# PCB-CARR-SL45.net
KiCad netlist of a schematic drawn in EAGLE
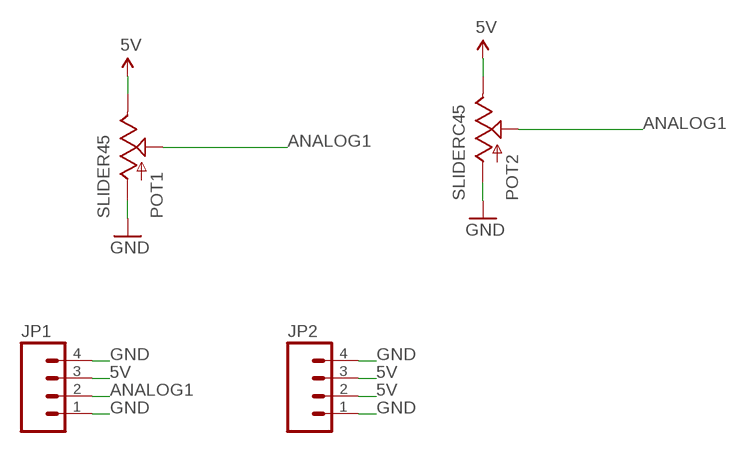
[diagram p0: schematic, sheet 1]

(export (version "E")
  (design (tool "Eeschema 10.0.6"))
  (components
    (comp (ref "JP1")
      (value "M04PTH")
      (footprint "eagle-import:1X04")
      (libsource (lib "eagle-import") (part "M04PTH"))
    )
    (comp (ref "JP2")
      (value "M04PTH")
      (footprint "eagle-import:1X04")
      (libsource (lib "eagle-import") (part "M04PTH"))
    )
    (comp (ref "POT1")
      (value "SLIDER45")
      (footprint "eagle-import:SLIDER45")
      (libsource (lib "eagle-import") (part "SLIDER45"))
    )
    (comp (ref "POT2")
      (value "SLIDERC45")
      (footprint "eagle-import:SLIDER45-CAR1")
      (libsource (lib "eagle-import") (part "SLIDERC45"))
    )
  )
  (nets
    (net (code "1") (name "/ANALOG1") (class "Default")
      (node (ref "JP1") (pin "2") (pinfunction "2_2") (pintype "passive"))
      (node (ref "POT1") (pin "2A") (pinfunction "S_2A") (pintype "passive"))
      (node (ref "POT2") (pin "2A") (pinfunction "S_2A") (pintype "passive"))
    )
    (net (code "2") (name "5V") (class "Default")
      (node (ref "JP1") (pin "3") (pinfunction "3_3") (pintype "passive"))
      (node (ref "JP2") (pin "2") (pinfunction "2_2") (pintype "passive"))
      (node (ref "JP2") (pin "3") (pinfunction "3_3") (pintype "passive"))
      (node (ref "POT1") (pin "1") (pinfunction "E_1") (pintype "passive"))
      (node (ref "POT2") (pin "1") (pinfunction "E_1") (pintype "passive"))
    )
    (net (code "3") (name "GND") (class "Default")
      (node (ref "JP1") (pin "1") (pinfunction "1_1") (pintype "passive"))
      (node (ref "JP1") (pin "4") (pinfunction "4_4") (pintype "passive"))
      (node (ref "JP2") (pin "1") (pinfunction "1_1") (pintype "passive"))
      (node (ref "JP2") (pin "4") (pinfunction "4_4") (pintype "passive"))
      (node (ref "POT1") (pin "3") (pinfunction "A_3") (pintype "passive"))
      (node (ref "POT2") (pin "3") (pinfunction "A_3") (pintype "passive"))
    )
  )
)
